# USB_Audio_Interface.net
KiCad netlist of a schematic drawn in EAGLE
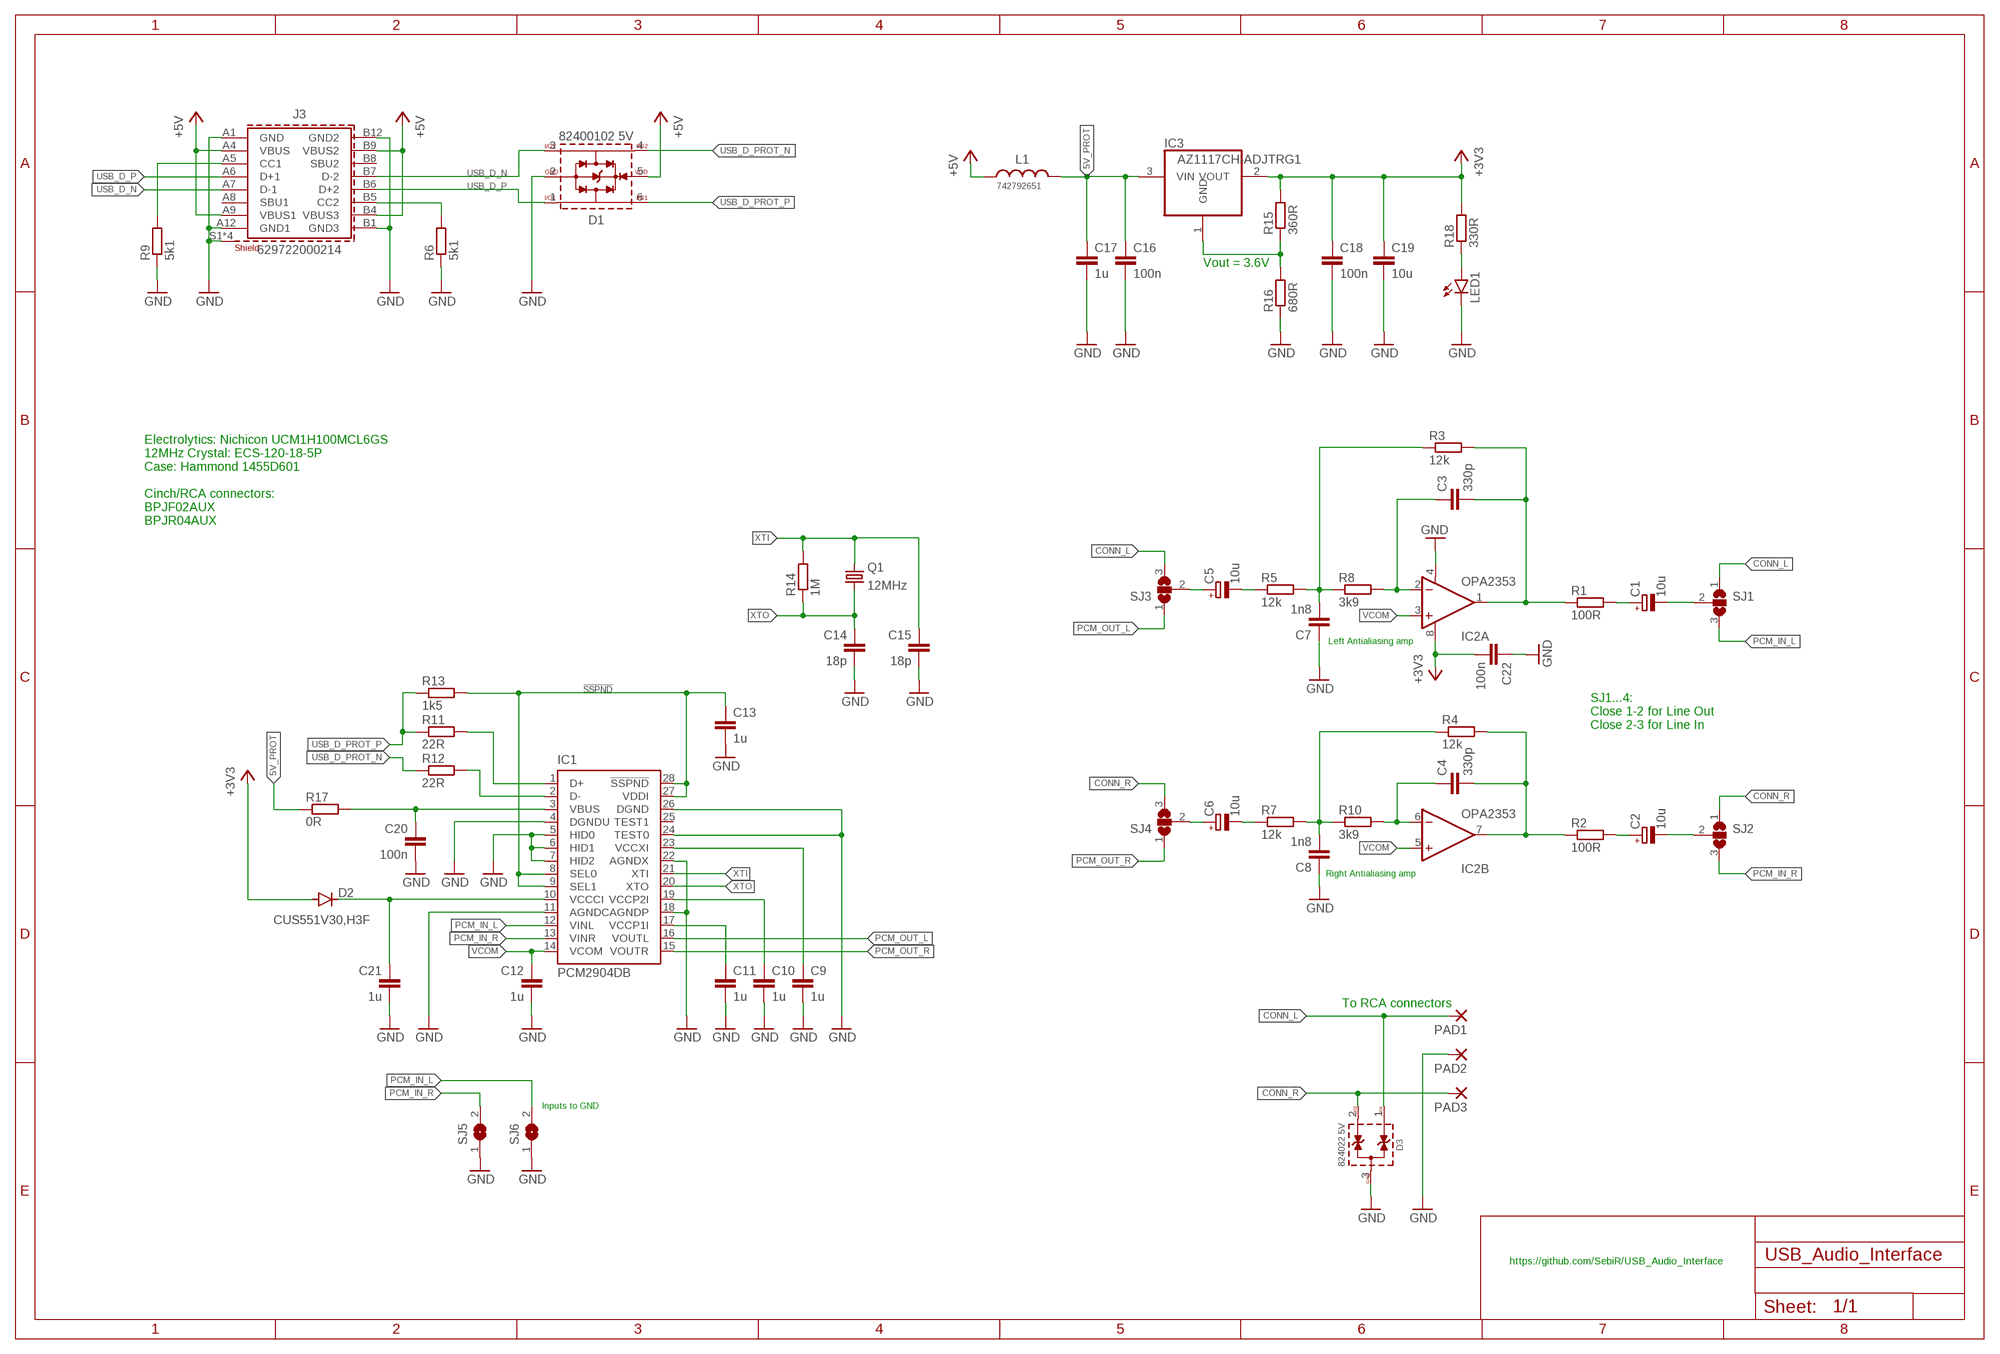
[diagram p0: schematic, sheet 1]

(export (version "E")
  (design (tool "Eeschema 10.0.6"))
  (components
    (comp (ref "C1")
      (value "10u")
      (footprint "eagle-import:UD-4X5,8_NICHICON")
      (libsource (lib "eagle-import") (part "CPOL-EUUD-4X5,8"))
    )
    (comp (ref "C2")
      (value "10u")
      (footprint "eagle-import:UD-4X5,8_NICHICON")
      (libsource (lib "eagle-import") (part "CPOL-EUUD-4X5,8"))
    )
    (comp (ref "C3")
      (value "330p")
      (footprint "eagle-import:C0603")
      (libsource (lib "eagle-import") (part "C-EUC0603"))
    )
    (comp (ref "C4")
      (value "330p")
      (footprint "eagle-import:C0603")
      (libsource (lib "eagle-import") (part "C-EUC0603"))
    )
    (comp (ref "C5")
      (value "10u")
      (footprint "eagle-import:UD-4X5,8_NICHICON")
      (libsource (lib "eagle-import") (part "CPOL-EUUD-4X5,8"))
    )
    (comp (ref "C6")
      (value "10u")
      (footprint "eagle-import:UD-4X5,8_NICHICON")
      (libsource (lib "eagle-import") (part "CPOL-EUUD-4X5,8"))
    )
    (comp (ref "C7")
      (value "1n8")
      (footprint "eagle-import:C0603")
      (libsource (lib "eagle-import") (part "C-EUC0603"))
    )
    (comp (ref "C8")
      (value "1n8")
      (footprint "eagle-import:C0603")
      (libsource (lib "eagle-import") (part "C-EUC0603"))
    )
    (comp (ref "C9")
      (value "1u")
      (footprint "eagle-import:C0603")
      (libsource (lib "eagle-import") (part "C-EUC0603"))
    )
    (comp (ref "C10")
      (value "1u")
      (footprint "eagle-import:C0603")
      (libsource (lib "eagle-import") (part "C-EUC0603"))
    )
    (comp (ref "C11")
      (value "1u")
      (footprint "eagle-import:C0603")
      (libsource (lib "eagle-import") (part "C-EUC0603"))
    )
    (comp (ref "C12")
      (value "1u")
      (footprint "eagle-import:C0603")
      (libsource (lib "eagle-import") (part "C-EUC0603"))
    )
    (comp (ref "C13")
      (value "1u")
      (footprint "eagle-import:C0603")
      (libsource (lib "eagle-import") (part "C-EUC0603"))
    )
    (comp (ref "C14")
      (value "18p")
      (footprint "eagle-import:C0603")
      (libsource (lib "eagle-import") (part "C-EUC0603"))
    )
    (comp (ref "C15")
      (value "18p")
      (footprint "eagle-import:C0603")
      (libsource (lib "eagle-import") (part "C-EUC0603"))
    )
    (comp (ref "C16")
      (value "100n")
      (footprint "eagle-import:C0603")
      (libsource (lib "eagle-import") (part "C-EUC0603"))
    )
    (comp (ref "C17")
      (value "1u")
      (footprint "eagle-import:C0603")
      (libsource (lib "eagle-import") (part "C-EUC0603"))
    )
    (comp (ref "C18")
      (value "100n")
      (footprint "eagle-import:C0603")
      (libsource (lib "eagle-import") (part "C-EUC0603"))
    )
    (comp (ref "C19")
      (value "10u")
      (footprint "eagle-import:C0603")
      (libsource (lib "eagle-import") (part "C-EUC0603"))
    )
    (comp (ref "C20")
      (value "100n")
      (footprint "eagle-import:C0603")
      (libsource (lib "eagle-import") (part "C-EUC0603"))
    )
    (comp (ref "C21")
      (value "1u")
      (footprint "eagle-import:C0603")
      (libsource (lib "eagle-import") (part "C-EUC0603"))
    )
    (comp (ref "C22")
      (value "100n")
      (footprint "eagle-import:C0603")
      (libsource (lib "eagle-import") (part "C-EUC0603"))
    )
    (comp (ref "D1")
      (value "82400102 5V")
      (footprint "eagle-import:WE-TVS_SOT23-6L")
      (libsource (lib "eagle-import") (part "WE-TVS-HS_SOT23-6L_82400102"))
    )
    (comp (ref "D2")
      (value "CUS551V30,H3F")
      (footprint "eagle-import:SOD323-R")
      (libsource (lib "eagle-import") (part "DIODE-SOD323-R"))
    )
    (comp (ref "D3")
      (value "824022 5V")
      (footprint "eagle-import:WE-TVS_SOT23-3L")
      (libsource (lib "eagle-import") (part "WE-TVS_SOT23-3L_824022"))
    )
    (comp (ref "IC1")
      (value "PCM2904DB")
      (footprint "eagle-import:SSOP28DB")
      (fields (field (name "MF") "TEXAS INSTRUMENT CONNECTORS"))
      (libsource (lib "eagle-import") (part "PCM2904DB"))
    )
    (comp (ref "IC2")
      (value "OPA2353")
      (footprint "eagle-import:SO08")
      (fields (field (name "MANUFACTURER") "TEXAS INSTRUMENTS") (field (name "MPN") "OPA2340UA"))
      (libsource (lib "eagle-import") (part "OPA2340U"))
    )
    (comp (ref "IC3")
      (value "AZ1117CH-ADJTRG1")
      (footprint "eagle-import:SOT223")
      (fields (field (name "MPN") "REG1117"))
      (libsource (lib "eagle-import") (part "REG1117"))
    )
    (comp (ref "J3")
      (value "629722000214")
      (footprint "eagle-import:629722000214")
      (libsource (lib "eagle-import") (part "629722000214"))
    )
    (comp (ref "L1")
      (value "742792651")
      (footprint "eagle-import:WE-CBF_0603_W2.6")
      (libsource (lib "eagle-import") (part "WE-CBF_0603_HC_742792651"))
    )
    (comp (ref "LED1")
      (value "LEDMICRO-SIDELED")
      (footprint "eagle-import:MICRO-SIDELED")
      (libsource (lib "eagle-import") (part "LEDMICRO-SIDELED"))
    )
    (comp (ref "PAD1")
      (value "2,15/1,0")
      (footprint "eagle-import:2,15_1,0")
      (libsource (lib "eagle-import") (part "2,15/1,0"))
    )
    (comp (ref "PAD2")
      (value "2,15/1,0")
      (footprint "eagle-import:2,15_1,0")
      (libsource (lib "eagle-import") (part "2,15/1,0"))
    )
    (comp (ref "PAD3")
      (value "2,15/1,0")
      (footprint "eagle-import:2,15_1,0")
      (libsource (lib "eagle-import") (part "2,15/1,0"))
    )
    (comp (ref "Q1")
      (value "12MHz")
      (footprint "eagle-import:HC49UP")
      (libsource (lib "eagle-import") (part "CRYSTALHC49UP"))
    )
    (comp (ref "R1")
      (value "100R")
      (footprint "eagle-import:R0603")
      (libsource (lib "eagle-import") (part "R-EU_R0603"))
    )
    (comp (ref "R2")
      (value "100R")
      (footprint "eagle-import:R0603")
      (libsource (lib "eagle-import") (part "R-EU_R0603"))
    )
    (comp (ref "R3")
      (value "12k")
      (footprint "eagle-import:R0603")
      (libsource (lib "eagle-import") (part "R-EU_R0603"))
    )
    (comp (ref "R4")
      (value "12k")
      (footprint "eagle-import:R0603")
      (libsource (lib "eagle-import") (part "R-EU_R0603"))
    )
    (comp (ref "R5")
      (value "12k")
      (footprint "eagle-import:R0603")
      (libsource (lib "eagle-import") (part "R-EU_R0603"))
    )
    (comp (ref "R6")
      (value "5k1")
      (footprint "eagle-import:R0603")
      (libsource (lib "eagle-import") (part "R-EU_R0603"))
    )
    (comp (ref "R7")
      (value "12k")
      (footprint "eagle-import:R0603")
      (libsource (lib "eagle-import") (part "R-EU_R0603"))
    )
    (comp (ref "R8")
      (value "3k9")
      (footprint "eagle-import:R0603")
      (libsource (lib "eagle-import") (part "R-EU_R0603"))
    )
    (comp (ref "R9")
      (value "5k1")
      (footprint "eagle-import:R0603")
      (libsource (lib "eagle-import") (part "R-EU_R0603"))
    )
    (comp (ref "R10")
      (value "3k9")
      (footprint "eagle-import:R0603")
      (libsource (lib "eagle-import") (part "R-EU_R0603"))
    )
    (comp (ref "R11")
      (value "22R")
      (footprint "eagle-import:R0603")
      (libsource (lib "eagle-import") (part "R-EU_R0603"))
    )
    (comp (ref "R12")
      (value "22R")
      (footprint "eagle-import:R0603")
      (libsource (lib "eagle-import") (part "R-EU_R0603"))
    )
    (comp (ref "R13")
      (value "1k5")
      (footprint "eagle-import:R0603")
      (libsource (lib "eagle-import") (part "R-EU_R0603"))
    )
    (comp (ref "R14")
      (value "1M")
      (footprint "eagle-import:R0603")
      (libsource (lib "eagle-import") (part "R-EU_R0603"))
    )
    (comp (ref "R15")
      (value "360R")
      (footprint "eagle-import:R0603")
      (libsource (lib "eagle-import") (part "R-EU_R0603"))
    )
    (comp (ref "R16")
      (value "680R")
      (footprint "eagle-import:R0603")
      (libsource (lib "eagle-import") (part "R-EU_R0603"))
    )
    (comp (ref "R17")
      (value "0R")
      (footprint "eagle-import:R0603")
      (libsource (lib "eagle-import") (part "R-EU_R0603"))
    )
    (comp (ref "R18")
      (value "330R")
      (footprint "eagle-import:R0603")
      (libsource (lib "eagle-import") (part "R-EU_R0603"))
    )
    (comp (ref "SJ1")
      (value "SJ2W")
      (footprint "eagle-import:SJ_2")
      (libsource (lib "eagle-import") (part "SJ2W"))
    )
    (comp (ref "SJ2")
      (value "SJ2W")
      (footprint "eagle-import:SJ_2")
      (libsource (lib "eagle-import") (part "SJ2W"))
    )
    (comp (ref "SJ3")
      (value "SJ2W")
      (footprint "eagle-import:SJ_2")
      (libsource (lib "eagle-import") (part "SJ2W"))
    )
    (comp (ref "SJ4")
      (value "SJ2W")
      (footprint "eagle-import:SJ_2")
      (libsource (lib "eagle-import") (part "SJ2W"))
    )
    (comp (ref "SJ5") (value "SJ") (footprint "eagle-import:SJ") (libsource (lib "eagle-import") (part "SJ")))
    (comp (ref "SJ6") (value "SJ") (footprint "eagle-import:SJ") (libsource (lib "eagle-import") (part "SJ")))
  )
  (nets
    (net (code "1") (name "+3V3") (class "Default")
      (node (ref "C18") (pin "1") (pinfunction "1_1") (pintype "passive"))
      (node (ref "C19") (pin "1") (pinfunction "1_1") (pintype "passive"))
      (node (ref "C22") (pin "2") (pinfunction "2_2") (pintype "passive"))
      (node (ref "D2") (pin "A") (pinfunction "A_A") (pintype "passive"))
      (node (ref "IC2") (pin "8") (pinfunction "V+_8") (pintype "power_in"))
      (node (ref "IC3") (pin "2") (pinfunction "VOUT_2") (pintype "output"))
      (node (ref "R15") (pin "2") (pinfunction "2_2") (pintype "passive"))
      (node (ref "R18") (pin "2") (pinfunction "2_2") (pintype "passive"))
    )
    (net (code "2") (name "+5V") (class "Default")
      (node (ref "D1") (pin "5") (pinfunction "VDD_5") (pintype "passive"))
      (node (ref "J3") (pin "A4") (pinfunction "VBUS_A4") (pintype "passive"))
      (node (ref "J3") (pin "A9") (pinfunction "VBUS1_A9") (pintype "passive"))
      (node (ref "J3") (pin "B4") (pinfunction "VBUS3_B4") (pintype "passive"))
      (node (ref "J3") (pin "B9") (pinfunction "VBUS2_B9") (pintype "passive"))
      (node (ref "L1") (pin "1") (pinfunction "1_1") (pintype "passive"))
    )
    (net (code "3") (name "/~{SSPND}") (class "Default")
      (node (ref "C13") (pin "1") (pinfunction "1_1") (pintype "passive"))
      (node (ref "IC1") (pin "27") (pinfunction "VDDI_27") (pintype "power_in"))
      (node (ref "IC1") (pin "28") (pinfunction "~{SSPND}_28") (pintype "output"))
      (node (ref "IC1") (pin "8") (pinfunction "SEL0_8") (pintype "input"))
      (node (ref "IC1") (pin "9") (pinfunction "SEL1_9") (pintype "input"))
      (node (ref "R13") (pin "2") (pinfunction "2_2") (pintype "passive"))
    )
    (net (code "4") (name "5V_PROT") (class "Default")
      (node (ref "C16") (pin "1") (pinfunction "1_1") (pintype "passive"))
      (node (ref "C17") (pin "1") (pinfunction "1_1") (pintype "passive"))
      (node (ref "IC3") (pin "3") (pinfunction "VIN_3") (pintype "input"))
      (node (ref "L1") (pin "2") (pinfunction "2_2") (pintype "passive"))
      (node (ref "R17") (pin "1") (pinfunction "1_1") (pintype "passive"))
    )
    (net (code "5") (name "CONN_L") (class "Default")
      (node (ref "D3") (pin "1") (pinfunction "I/O1_1") (pintype "passive"))
      (node (ref "PAD1") (pin "1") (pinfunction "P_1") (pintype "passive"))
      (node (ref "SJ1") (pin "1") (pinfunction "1_1") (pintype "passive"))
      (node (ref "SJ3") (pin "3") (pinfunction "3_3") (pintype "passive"))
    )
    (net (code "6") (name "CONN_R") (class "Default")
      (node (ref "D3") (pin "2") (pinfunction "I/O2_2") (pintype "passive"))
      (node (ref "PAD3") (pin "1") (pinfunction "P_1") (pintype "passive"))
      (node (ref "SJ2") (pin "1") (pinfunction "1_1") (pintype "passive"))
      (node (ref "SJ4") (pin "3") (pinfunction "3_3") (pintype "passive"))
    )
    (net (code "7") (name "GND") (class "Default")
      (node (ref "C10") (pin "2") (pinfunction "2_2") (pintype "passive"))
      (node (ref "C11") (pin "2") (pinfunction "2_2") (pintype "passive"))
      (node (ref "C12") (pin "2") (pinfunction "2_2") (pintype "passive"))
      (node (ref "C13") (pin "2") (pinfunction "2_2") (pintype "passive"))
      (node (ref "C14") (pin "2") (pinfunction "2_2") (pintype "passive"))
      (node (ref "C15") (pin "2") (pinfunction "2_2") (pintype "passive"))
      (node (ref "C16") (pin "2") (pinfunction "2_2") (pintype "passive"))
      (node (ref "C17") (pin "2") (pinfunction "2_2") (pintype "passive"))
      (node (ref "C18") (pin "2") (pinfunction "2_2") (pintype "passive"))
      (node (ref "C19") (pin "2") (pinfunction "2_2") (pintype "passive"))
      (node (ref "C20") (pin "2") (pinfunction "2_2") (pintype "passive"))
      (node (ref "C21") (pin "2") (pinfunction "2_2") (pintype "passive"))
      (node (ref "C22") (pin "1") (pinfunction "1_1") (pintype "passive"))
      (node (ref "C7") (pin "1") (pinfunction "1_1") (pintype "passive"))
      (node (ref "C8") (pin "1") (pinfunction "1_1") (pintype "passive"))
      (node (ref "C9") (pin "2") (pinfunction "2_2") (pintype "passive"))
      (node (ref "D1") (pin "2") (pinfunction "GND_2") (pintype "passive"))
      (node (ref "D3") (pin "3") (pinfunction "GND_3") (pintype "passive"))
      (node (ref "IC1") (pin "11") (pinfunction "AGNDC_11") (pintype "power_in"))
      (node (ref "IC1") (pin "18") (pinfunction "AGNDP_18") (pintype "power_in"))
      (node (ref "IC1") (pin "22") (pinfunction "AGNDX_22") (pintype "power_in"))
      (node (ref "IC1") (pin "24") (pinfunction "TEST0_24") (pintype "input"))
      (node (ref "IC1") (pin "26") (pinfunction "DGND_26") (pintype "power_in"))
      (node (ref "IC1") (pin "4") (pinfunction "DGNDU_4") (pintype "power_in"))
      (node (ref "IC1") (pin "5") (pinfunction "HID0_5") (pintype "input"))
      (node (ref "IC1") (pin "6") (pinfunction "HID1_6") (pintype "input"))
      (node (ref "IC1") (pin "7") (pinfunction "HID2_7") (pintype "input"))
      (node (ref "IC2") (pin "4") (pinfunction "V-_4") (pintype "power_in"))
      (node (ref "J3") (pin "A1") (pinfunction "GND_A1") (pintype "passive"))
      (node (ref "J3") (pin "A12") (pinfunction "GND1_A12") (pintype "passive"))
      (node (ref "J3") (pin "B1") (pinfunction "GND3_B1") (pintype "passive"))
      (node (ref "J3") (pin "B12") (pinfunction "GND2_B12") (pintype "passive"))
      (node (ref "J3") (pin "S1") (pinfunction "SHIELD_S1") (pintype "passive"))
      (node (ref "J3") (pin "S2") (pinfunction "SHIELD_S2") (pintype "passive"))
      (node (ref "J3") (pin "S3") (pinfunction "SHIELD_S3") (pintype "passive"))
      (node (ref "J3") (pin "S4") (pinfunction "SHIELD_S4") (pintype "passive"))
      (node (ref "LED1") (pin "C") (pinfunction "C_C") (pintype "passive"))
      (node (ref "PAD2") (pin "1") (pinfunction "P_1") (pintype "passive"))
      (node (ref "R16") (pin "1") (pinfunction "1_1") (pintype "passive"))
      (node (ref "R6") (pin "1") (pinfunction "1_1") (pintype "passive"))
      (node (ref "R9") (pin "1") (pinfunction "1_1") (pintype "passive"))
      (node (ref "SJ5") (pin "1") (pinfunction "1_1") (pintype "passive"))
      (node (ref "SJ6") (pin "1") (pinfunction "1_1") (pintype "passive"))
    )
    (net (code "8") (name "Net-(C1-Pad+)") (class "Default")
      (node (ref "C1") (pin "+") (pinfunction "+_+") (pintype "passive"))
      (node (ref "R1") (pin "2") (pinfunction "2_2") (pintype "passive"))
    )
    (net (code "9") (name "Net-(C1-Pad-)") (class "Default")
      (node (ref "C1") (pin "-") (pinfunction "-_-") (pintype "passive"))
      (node (ref "SJ1") (pin "2") (pinfunction "2_2") (pintype "passive"))
    )
    (net (code "10") (name "Net-(C2-Pad+)") (class "Default")
      (node (ref "C2") (pin "+") (pinfunction "+_+") (pintype "passive"))
      (node (ref "R2") (pin "2") (pinfunction "2_2") (pintype "passive"))
    )
    (net (code "11") (name "Net-(C2-Pad-)") (class "Default")
      (node (ref "C2") (pin "-") (pinfunction "-_-") (pintype "passive"))
      (node (ref "SJ2") (pin "2") (pinfunction "2_2") (pintype "passive"))
    )
    (net (code "12") (name "Net-(C5-Pad+)") (class "Default")
      (node (ref "C5") (pin "+") (pinfunction "+_+") (pintype "passive"))
      (node (ref "SJ3") (pin "2") (pinfunction "2_2") (pintype "passive"))
    )
    (net (code "13") (name "Net-(C5-Pad-)") (class "Default")
      (node (ref "C5") (pin "-") (pinfunction "-_-") (pintype "passive"))
      (node (ref "R5") (pin "1") (pinfunction "1_1") (pintype "passive"))
    )
    (net (code "14") (name "Net-(C6-Pad+)") (class "Default")
      (node (ref "C6") (pin "+") (pinfunction "+_+") (pintype "passive"))
      (node (ref "SJ4") (pin "2") (pinfunction "2_2") (pintype "passive"))
    )
    (net (code "15") (name "Net-(C6-Pad-)") (class "Default")
      (node (ref "C6") (pin "-") (pinfunction "-_-") (pintype "passive"))
      (node (ref "R7") (pin "1") (pinfunction "1_1") (pintype "passive"))
    )
    (net (code "16") (name "Net-(C7-Pad2)") (class "Default")
      (node (ref "C7") (pin "2") (pinfunction "2_2") (pintype "passive"))
      (node (ref "R3") (pin "1") (pinfunction "1_1") (pintype "passive"))
      (node (ref "R5") (pin "2") (pinfunction "2_2") (pintype "passive"))
      (node (ref "R8") (pin "1") (pinfunction "1_1") (pintype "passive"))
    )
    (net (code "17") (name "Net-(C8-Pad2)") (class "Default")
      (node (ref "C8") (pin "2") (pinfunction "2_2") (pintype "passive"))
      (node (ref "R10") (pin "1") (pinfunction "1_1") (pintype "passive"))
      (node (ref "R4") (pin "1") (pinfunction "1_1") (pintype "passive"))
      (node (ref "R7") (pin "2") (pinfunction "2_2") (pintype "passive"))
    )
    (net (code "18") (name "Net-(IC1-D+)") (class "Default")
      (node (ref "IC1") (pin "1") (pinfunction "D+_1") (pintype "bidirectional"))
      (node (ref "R11") (pin "2") (pinfunction "2_2") (pintype "passive"))
    )
    (net (code "19") (name "Net-(IC1-D-)") (class "Default")
      (node (ref "IC1") (pin "2") (pinfunction "D-_2") (pintype "bidirectional"))
      (node (ref "R12") (pin "2") (pinfunction "2_2") (pintype "passive"))
    )
    (net (code "20") (name "Net-(IC1-VBUS)") (class "Default")
      (node (ref "C20") (pin "1") (pinfunction "1_1") (pintype "passive"))
      (node (ref "IC1") (pin "3") (pinfunction "VBUS_3") (pintype "power_in"))
      (node (ref "R17") (pin "2") (pinfunction "2_2") (pintype "passive"))
    )
    (net (code "21") (name "Net-(IC1-VCCCI)") (class "Default")
      (node (ref "C21") (pin "1") (pinfunction "1_1") (pintype "passive"))
      (node (ref "D2") (pin "C") (pinfunction "C_C") (pintype "passive"))
      (node (ref "IC1") (pin "10") (pinfunction "VCCCI_10") (pintype "power_in"))
    )
    (net (code "22") (name "Net-(IC1-VCCP1I)") (class "Default")
      (node (ref "C11") (pin "1") (pinfunction "1_1") (pintype "passive"))
      (node (ref "IC1") (pin "17") (pinfunction "VCCP1I_17") (pintype "input"))
    )
    (net (code "23") (name "Net-(IC1-VCCP2I)") (class "Default")
      (node (ref "C10") (pin "1") (pinfunction "1_1") (pintype "passive"))
      (node (ref "IC1") (pin "19") (pinfunction "VCCP2I_19") (pintype "power_in"))
    )
    (net (code "24") (name "Net-(IC1-VCCXI)") (class "Default")
      (node (ref "C9") (pin "1") (pinfunction "1_1") (pintype "passive"))
      (node (ref "IC1") (pin "23") (pinfunction "VCCXI_23") (pintype "power_in"))
    )
    (net (code "25") (name "Net-(IC2A--IN)") (class "Default")
      (node (ref "C3") (pin "1") (pinfunction "1_1") (pintype "passive"))
      (node (ref "IC2") (pin "2") (pinfunction "-IN_2") (pintype "input"))
      (node (ref "R8") (pin "2") (pinfunction "2_2") (pintype "passive"))
    )
    (net (code "26") (name "Net-(IC2A-OUT)") (class "Default")
      (node (ref "C3") (pin "2") (pinfunction "2_2") (pintype "passive"))
      (node (ref "IC2") (pin "1") (pinfunction "OUT_1") (pintype "output"))
      (node (ref "R1") (pin "1") (pinfunction "1_1") (pintype "passive"))
      (node (ref "R3") (pin "2") (pinfunction "2_2") (pintype "passive"))
    )
    (net (code "27") (name "Net-(IC2B--IN)") (class "Default")
      (node (ref "C4") (pin "1") (pinfunction "1_1") (pintype "passive"))
      (node (ref "IC2") (pin "6") (pinfunction "-IN_6") (pintype "input"))
      (node (ref "R10") (pin "2") (pinfunction "2_2") (pintype "passive"))
    )
    (net (code "28") (name "Net-(IC2B-OUT)") (class "Default")
      (node (ref "C4") (pin "2") (pinfunction "2_2") (pintype "passive"))
      (node (ref "IC2") (pin "7") (pinfunction "OUT_7") (pintype "output"))
      (node (ref "R2") (pin "1") (pinfunction "1_1") (pintype "passive"))
      (node (ref "R4") (pin "2") (pinfunction "2_2") (pintype "passive"))
    )
    (net (code "29") (name "Net-(IC3-GND)") (class "Default")
      (node (ref "IC3") (pin "1") (pinfunction "GND_1") (pintype "power_in"))
      (node (ref "R15") (pin "1") (pinfunction "1_1") (pintype "passive"))
      (node (ref "R16") (pin "2") (pinfunction "2_2") (pintype "passive"))
    )
    (net (code "30") (name "Net-(J3-CC1)") (class "Default")
      (node (ref "J3") (pin "A5") (pinfunction "CC1_A5") (pintype "passive"))
      (node (ref "R9") (pin "2") (pinfunction "2_2") (pintype "passive"))
    )
    (net (code "31") (name "Net-(J3-CC2)") (class "Default")
      (node (ref "J3") (pin "B5") (pinfunction "CC2_B5") (pintype "passive"))
      (node (ref "R6") (pin "2") (pinfunction "2_2") (pintype "passive"))
    )
    (net (code "32") (name "Net-(LED1-PadA)") (class "Default")
      (node (ref "LED1") (pin "A") (pinfunction "A_A") (pintype "passive"))
      (node (ref "R18") (pin "1") (pinfunction "1_1") (pintype "passive"))
    )
    (net (code "33") (name "PCM_IN_L") (class "Default")
      (node (ref "IC1") (pin "12") (pinfunction "VINL_12") (pintype "input"))
      (node (ref "SJ1") (pin "3") (pinfunction "3_3") (pintype "passive"))
      (node (ref "SJ6") (pin "2") (pinfunction "2_2") (pintype "passive"))
    )
    (net (code "34") (name "PCM_IN_R") (class "Default")
      (node (ref "IC1") (pin "13") (pinfunction "VINR_13") (pintype "input"))
      (node (ref "SJ2") (pin "3") (pinfunction "3_3") (pintype "passive"))
      (node (ref "SJ5") (pin "2") (pinfunction "2_2") (pintype "passive"))
    )
    (net (code "35") (name "PCM_OUT_L") (class "Default")
      (node (ref "IC1") (pin "16") (pinfunction "VOUTL_16") (pintype "output"))
      (node (ref "SJ3") (pin "1") (pinfunction "1_1") (pintype "passive"))
    )
    (net (code "36") (name "PCM_OUT_R") (class "Default")
      (node (ref "IC1") (pin "15") (pinfunction "VOUTR_15") (pintype "output"))
      (node (ref "SJ4") (pin "1") (pinfunction "1_1") (pintype "passive"))
    )
    (net (code "37") (name "USB_D_N") (class "Default")
      (node (ref "D1") (pin "3") (pinfunction "I/O2_3") (pintype "passive"))
      (node (ref "J3") (pin "A7") (pinfunction "D-1_A7") (pintype "passive"))
      (node (ref "J3") (pin "B7") (pinfunction "D-2_B7") (pintype "passive"))
    )
    (net (code "38") (name "USB_D_P") (class "Default")
      (node (ref "D1") (pin "1") (pinfunction "I/O1_1") (pintype "passive"))
      (node (ref "J3") (pin "A6") (pinfunction "D+1_A6") (pintype "passive"))
      (node (ref "J3") (pin "B6") (pinfunction "D+2_B6") (pintype "passive"))
    )
    (net (code "39") (name "USB_D_PROT_N") (class "Default")
      (node (ref "D1") (pin "4") (pinfunction "I/O4_4") (pintype "passive"))
      (node (ref "R12") (pin "1") (pinfunction "1_1") (pintype "passive"))
    )
    (net (code "40") (name "USB_D_PROT_P") (class "Default")
      (node (ref "D1") (pin "6") (pinfunction "I/O3_6") (pintype "passive"))
      (node (ref "R11") (pin "1") (pinfunction "1_1") (pintype "passive"))
      (node (ref "R13") (pin "1") (pinfunction "1_1") (pintype "passive"))
    )
    (net (code "41") (name "VCOM") (class "Default")
      (node (ref "C12") (pin "1") (pinfunction "1_1") (pintype "passive"))
      (node (ref "IC1") (pin "14") (pinfunction "VCOM_14") (pintype "power_in"))
      (node (ref "IC2") (pin "3") (pinfunction "+IN_3") (pintype "input"))
      (node (ref "IC2") (pin "5") (pinfunction "+IN_5") (pintype "input"))
    )
    (net (code "42") (name "XTI") (class "Default")
      (node (ref "C15") (pin "1") (pinfunction "1_1") (pintype "passive"))
      (node (ref "IC1") (pin "21") (pinfunction "XTI_21") (pintype "input"))
      (node (ref "Q1") (pin "2") (pinfunction "2_2") (pintype "passive"))
      (node (ref "R14") (pin "2") (pinfunction "2_2") (pintype "passive"))
    )
    (net (code "43") (name "XTO") (class "Default")
      (node (ref "C14") (pin "1") (pinfunction "1_1") (pintype "passive"))
      (node (ref "IC1") (pin "20") (pinfunction "XTO_20") (pintype "output"))
      (node (ref "Q1") (pin "1") (pinfunction "1_1") (pintype "passive"))
      (node (ref "R14") (pin "1") (pinfunction "1_1") (pintype "passive"))
    )
    (net (code "44") (name "unconnected-(IC1-TEST1-Pad25)") (class "Default")
      (node (ref "IC1") (pin "25") (pinfunction "TEST1_25") (pintype "output"))
    )
    (net (code "45") (name "unconnected-(J3-SBU1-PadA8)") (class "Default")
      (node (ref "J3") (pin "A8") (pinfunction "SBU1_A8") (pintype "passive"))
    )
    (net (code "46") (name "unconnected-(J3-SBU2-PadB8)") (class "Default")
      (node (ref "J3") (pin "B8") (pinfunction "SBU2_B8") (pintype "passive"))
    )
  )
)
